# 12_LMS2_Power.net
KiCad netlist of a schematic drawn in Altium Designer
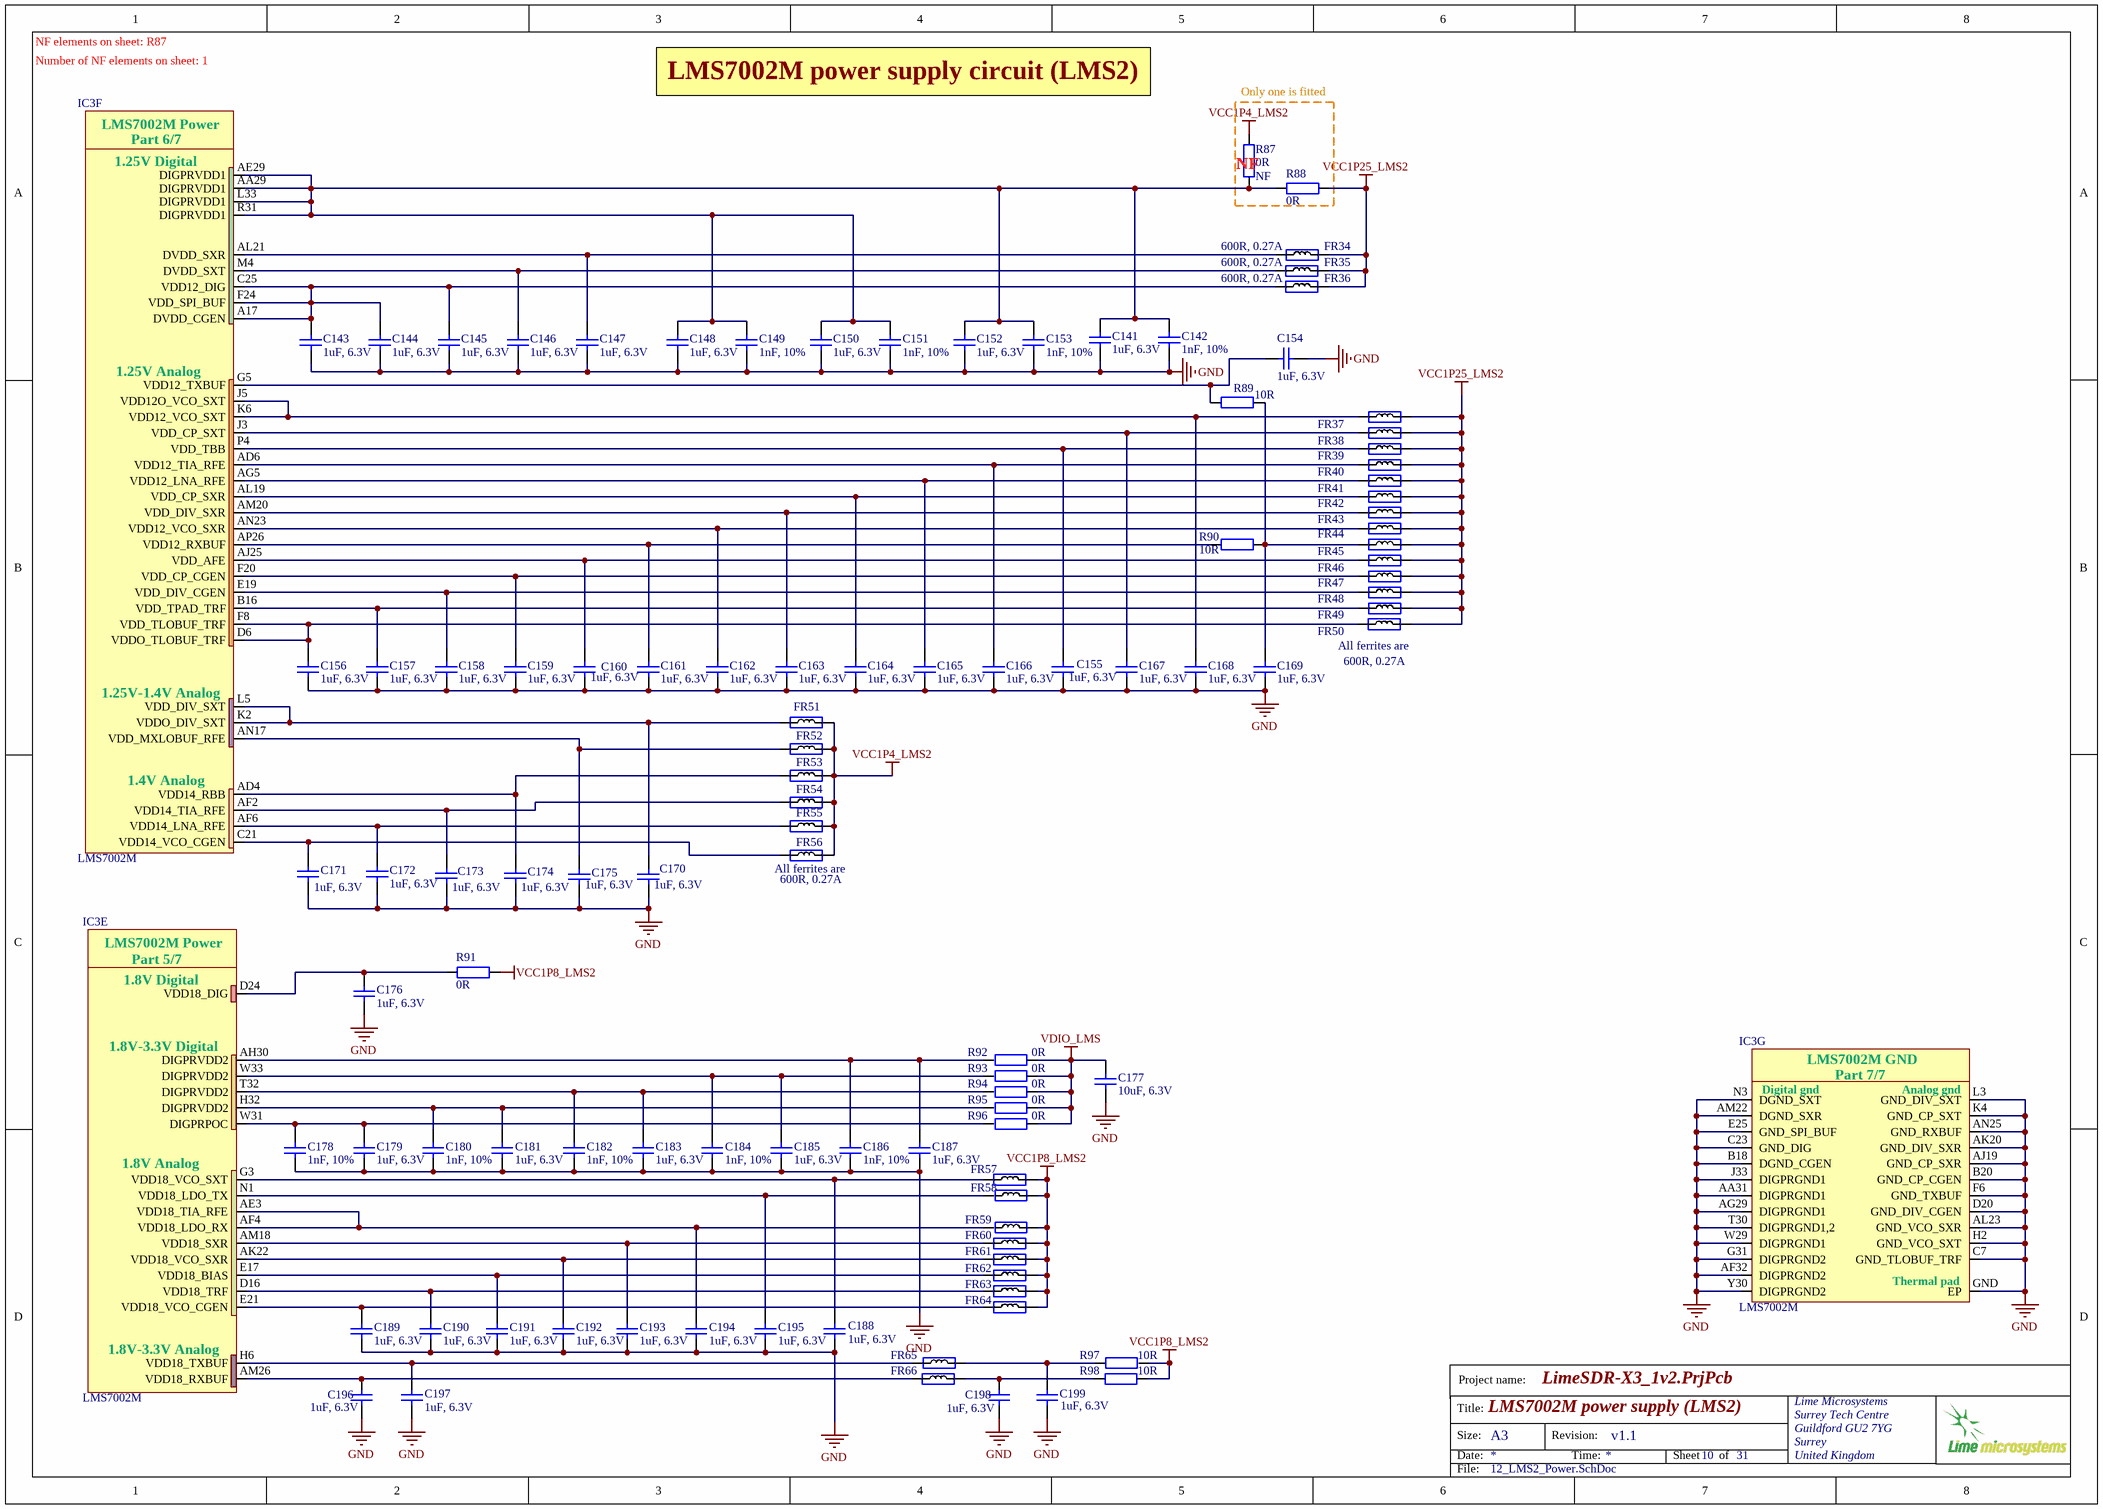
[diagram p0: 12_LMS2_Power.SchDoc]

(export (version "E")
  (design (tool "Eeschema 10.0.6"))
  (components
    (comp (ref "C141")
      (value "1uF, 6.3V")
      (footprint "CAP0201")
      (fields (field (name "TOLERANCE") "±20%") (field (name "MANUFACTURER") "TDK Corporation"))
      (libsource (lib "LimeMicroAltiumLib_schLib") (part "Cap_0402"))
    )
    (comp (ref "C142")
      (value "1nF, 10%")
      (footprint "CAP0201")
      (fields (field (name "TOLERANCE") "±10%") (field (name "MANUFACTURER") "TDK Corporation"))
      (libsource (lib "LimeMicroAltiumLib_schLib") (part "Cap_0402"))
    )
    (comp (ref "C143")
      (value "1uF, 6.3V")
      (footprint "CAP0201")
      (fields (field (name "TOLERANCE") "±20%") (field (name "MANUFACTURER") "TDK Corporation"))
      (libsource (lib "") (part "Cap_0402_2"))
    )
    (comp (ref "C144")
      (value "1uF, 6.3V")
      (footprint "CAP0201")
      (fields (field (name "TOLERANCE") "±20%") (field (name "MANUFACTURER") "TDK Corporation"))
      (libsource (lib "") (part "Cap_0402_2"))
    )
    (comp (ref "C145")
      (value "1uF, 6.3V")
      (footprint "CAP0201")
      (fields (field (name "TOLERANCE") "±20%") (field (name "MANUFACTURER") "TDK Corporation"))
      (libsource (lib "") (part "Cap_0402_2"))
    )
    (comp (ref "C146")
      (value "1uF, 6.3V")
      (footprint "CAP0201")
      (fields (field (name "TOLERANCE") "±20%") (field (name "MANUFACTURER") "TDK Corporation"))
      (libsource (lib "LimeMicroAltiumLib_schLib") (part "Cap_0402"))
    )
    (comp (ref "C147")
      (value "1uF, 6.3V")
      (footprint "CAP0201")
      (fields (field (name "TOLERANCE") "±20%") (field (name "MANUFACTURER") "TDK Corporation"))
      (libsource (lib "") (part "Cap_0402_2"))
    )
    (comp (ref "C148")
      (value "1uF, 6.3V")
      (footprint "CAP0201")
      (fields (field (name "TOLERANCE") "±20%") (field (name "MANUFACTURER") "TDK Corporation"))
      (libsource (lib "LimeMicroAltiumLib_schLib") (part "Cap_0402"))
    )
    (comp (ref "C149")
      (value "1nF, 10%")
      (footprint "CAP0201")
      (fields (field (name "TOLERANCE") "±10%") (field (name "MANUFACTURER") "TDK Corporation"))
      (libsource (lib "LimeMicroAltiumLib_schLib") (part "Cap_0402"))
    )
    (comp (ref "C150")
      (value "1uF, 6.3V")
      (footprint "CAP0201")
      (fields (field (name "TOLERANCE") "±20%") (field (name "MANUFACTURER") "TDK Corporation"))
      (libsource (lib "LimeMicroAltiumLib_schLib") (part "Cap_0402"))
    )
    (comp (ref "C151")
      (value "1nF, 10%")
      (footprint "CAP0201")
      (fields (field (name "TOLERANCE") "±10%") (field (name "MANUFACTURER") "TDK Corporation"))
      (libsource (lib "LimeMicroAltiumLib_schLib") (part "Cap_0402"))
    )
    (comp (ref "C152")
      (value "1uF, 6.3V")
      (footprint "CAP0201")
      (fields (field (name "TOLERANCE") "±20%") (field (name "MANUFACTURER") "TDK Corporation"))
      (libsource (lib "LimeMicroAltiumLib_schLib") (part "Cap_0402"))
    )
    (comp (ref "C153")
      (value "1nF, 10%")
      (footprint "CAP0201")
      (fields (field (name "TOLERANCE") "±10%") (field (name "MANUFACTURER") "TDK Corporation"))
      (libsource (lib "LimeMicroAltiumLib_schLib") (part "Cap_0402"))
    )
    (comp (ref "C154")
      (value "1uF, 6.3V")
      (footprint "CAP0201")
      (fields (field (name "TOLERANCE") "±20%") (field (name "MANUFACTURER") "TDK Corporation"))
      (libsource (lib "") (part "Cap_0402_3"))
    )
    (comp (ref "C155")
      (value "1uF, 6.3V")
      (footprint "CAP0201")
      (fields (field (name "TOLERANCE") "±20%") (field (name "MANUFACTURER") "TDK Corporation"))
      (libsource (lib "") (part "Cap_0402_2"))
    )
    (comp (ref "C156")
      (value "1uF, 6.3V")
      (footprint "CAP0201")
      (fields (field (name "TOLERANCE") "±20%") (field (name "MANUFACTURER") "TDK Corporation"))
      (libsource (lib "") (part "Cap_0402_2"))
    )
    (comp (ref "C157")
      (value "1uF, 6.3V")
      (footprint "CAP0201")
      (fields (field (name "TOLERANCE") "±20%") (field (name "MANUFACTURER") "TDK Corporation"))
      (libsource (lib "") (part "Cap_0402_2"))
    )
    (comp (ref "C158")
      (value "1uF, 6.3V")
      (footprint "CAP0201")
      (fields (field (name "TOLERANCE") "±20%") (field (name "MANUFACTURER") "TDK Corporation"))
      (libsource (lib "") (part "Cap_0402_2"))
    )
    (comp (ref "C159")
      (value "1uF, 6.3V")
      (footprint "CAP0201")
      (fields (field (name "TOLERANCE") "±20%") (field (name "MANUFACTURER") "TDK Corporation"))
      (libsource (lib "LimeMicroAltiumLib_schLib") (part "Cap_0402"))
    )
    (comp (ref "C160")
      (value "1uF, 6.3V")
      (footprint "CAP0201")
      (fields (field (name "TOLERANCE") "±20%") (field (name "MANUFACTURER") "TDK Corporation"))
      (libsource (lib "") (part "Cap_0402_2"))
    )
    (comp (ref "C161")
      (value "1uF, 6.3V")
      (footprint "CAP0201")
      (fields (field (name "TOLERANCE") "±20%") (field (name "MANUFACTURER") "TDK Corporation"))
      (libsource (lib "") (part "Cap_0402_2"))
    )
    (comp (ref "C162")
      (value "1uF, 6.3V")
      (footprint "CAP0201")
      (fields (field (name "TOLERANCE") "±20%") (field (name "MANUFACTURER") "TDK Corporation"))
      (libsource (lib "") (part "Cap_0402_2"))
    )
    (comp (ref "C163")
      (value "1uF, 6.3V")
      (footprint "CAP0201")
      (fields (field (name "TOLERANCE") "±20%") (field (name "MANUFACTURER") "TDK Corporation"))
      (libsource (lib "") (part "Cap_0402_2"))
    )
    (comp (ref "C164")
      (value "1uF, 6.3V")
      (footprint "CAP0201")
      (fields (field (name "TOLERANCE") "±20%") (field (name "MANUFACTURER") "TDK Corporation"))
      (libsource (lib "") (part "Cap_0402_2"))
    )
    (comp (ref "C165")
      (value "1uF, 6.3V")
      (footprint "CAP0201")
      (fields (field (name "TOLERANCE") "±20%") (field (name "MANUFACTURER") "TDK Corporation"))
      (libsource (lib "") (part "Cap_0402_2"))
    )
    (comp (ref "C166")
      (value "1uF, 6.3V")
      (footprint "CAP0201")
      (fields (field (name "TOLERANCE") "±20%") (field (name "MANUFACTURER") "TDK Corporation"))
      (libsource (lib "LimeMicroAltiumLib_schLib") (part "Cap_0402"))
    )
    (comp (ref "C167")
      (value "1uF, 6.3V")
      (footprint "CAP0201")
      (fields (field (name "TOLERANCE") "±20%") (field (name "MANUFACTURER") "TDK Corporation"))
      (libsource (lib "") (part "Cap_0402_2"))
    )
    (comp (ref "C168")
      (value "1uF, 6.3V")
      (footprint "CAP0201")
      (fields (field (name "TOLERANCE") "±20%") (field (name "MANUFACTURER") "TDK Corporation"))
      (libsource (lib "LimeMicroAltiumLib_schLib") (part "Cap_0402"))
    )
    (comp (ref "C169")
      (value "1uF, 6.3V")
      (footprint "CAP0201")
      (fields (field (name "TOLERANCE") "±20%") (field (name "MANUFACTURER") "TDK Corporation"))
      (libsource (lib "LimeMicroAltiumLib_schLib") (part "Cap_0402"))
    )
    (comp (ref "C170")
      (value "1uF, 6.3V")
      (footprint "CAP0201")
      (fields (field (name "TOLERANCE") "±20%") (field (name "MANUFACTURER") "TDK Corporation"))
      (libsource (lib "") (part "Cap_0402_2"))
    )
    (comp (ref "C171")
      (value "1uF, 6.3V")
      (footprint "CAP0201")
      (fields (field (name "TOLERANCE") "±20%") (field (name "MANUFACTURER") "TDK Corporation"))
      (libsource (lib "") (part "Cap_0402_2"))
    )
    (comp (ref "C172")
      (value "1uF, 6.3V")
      (footprint "CAP0201")
      (fields (field (name "TOLERANCE") "±20%") (field (name "MANUFACTURER") "TDK Corporation"))
      (libsource (lib "") (part "Cap_0402_2"))
    )
    (comp (ref "C173")
      (value "1uF, 6.3V")
      (footprint "CAP0201")
      (fields (field (name "TOLERANCE") "±20%") (field (name "MANUFACTURER") "TDK Corporation"))
      (libsource (lib "") (part "Cap_0402_4"))
    )
    (comp (ref "C174")
      (value "1uF, 6.3V")
      (footprint "CAP0201")
      (fields (field (name "TOLERANCE") "±20%") (field (name "MANUFACTURER") "TDK Corporation"))
      (libsource (lib "") (part "Cap_0402_4"))
    )
    (comp (ref "C175")
      (value "1uF, 6.3V")
      (footprint "CAP0201")
      (fields (field (name "TOLERANCE") "±20%") (field (name "MANUFACTURER") "TDK Corporation"))
      (libsource (lib "") (part "Cap_0402_2"))
    )
    (comp (ref "C176")
      (value "1uF, 6.3V")
      (footprint "CAP0201")
      (fields (field (name "TOLERANCE") "±20%") (field (name "MANUFACTURER") "TDK Corporation"))
      (libsource (lib "") (part "Cap_0402_1"))
    )
    (comp (ref "C177")
      (value "10uF, 6.3V")
      (footprint "CAP0603")
      (fields (field (name "TOLERANCE") "±20%") (field (name "MANUFACTURER") "Yageo"))
      (libsource (lib "LimeFPGAboard_schLib") (part "Cap_0603"))
    )
    (comp (ref "C178")
      (value "1nF, 10%")
      (footprint "CAP0201")
      (fields (field (name "TOLERANCE") "±10%") (field (name "MANUFACTURER") "TDK Corporation"))
      (libsource (lib "") (part "Cap_0402_1"))
    )
    (comp (ref "C179")
      (value "1uF, 6.3V")
      (footprint "CAP0201")
      (fields (field (name "TOLERANCE") "±20%") (field (name "MANUFACTURER") "TDK Corporation"))
      (libsource (lib "") (part "Cap_0402_1"))
    )
    (comp (ref "C180")
      (value "1nF, 10%")
      (footprint "CAP0201")
      (fields (field (name "TOLERANCE") "±10%") (field (name "MANUFACTURER") "TDK Corporation"))
      (libsource (lib "") (part "Cap_0402_1"))
    )
    (comp (ref "C181")
      (value "1uF, 6.3V")
      (footprint "CAP0201")
      (fields (field (name "TOLERANCE") "±20%") (field (name "MANUFACTURER") "TDK Corporation"))
      (libsource (lib "") (part "Cap_0402_1"))
    )
    (comp (ref "C182")
      (value "1nF, 10%")
      (footprint "CAP0201")
      (fields (field (name "TOLERANCE") "±10%") (field (name "MANUFACTURER") "TDK Corporation"))
      (libsource (lib "") (part "Cap_0402_1"))
    )
    (comp (ref "C183")
      (value "1uF, 6.3V")
      (footprint "CAP0201")
      (fields (field (name "TOLERANCE") "±20%") (field (name "MANUFACTURER") "TDK Corporation"))
      (libsource (lib "") (part "Cap_0402_1"))
    )
    (comp (ref "C184")
      (value "1nF, 10%")
      (footprint "CAP0201")
      (fields (field (name "TOLERANCE") "±10%") (field (name "MANUFACTURER") "TDK Corporation"))
      (libsource (lib "") (part "Cap_0402_1"))
    )
    (comp (ref "C185")
      (value "1uF, 6.3V")
      (footprint "CAP0201")
      (fields (field (name "TOLERANCE") "±20%") (field (name "MANUFACTURER") "TDK Corporation"))
      (libsource (lib "") (part "Cap_0402_1"))
    )
    (comp (ref "C186")
      (value "1nF, 10%")
      (footprint "CAP0201")
      (fields (field (name "TOLERANCE") "±10%") (field (name "MANUFACTURER") "TDK Corporation"))
      (libsource (lib "") (part "Cap_0402_1"))
    )
    (comp (ref "C187")
      (value "1uF, 6.3V")
      (footprint "CAP0201")
      (fields (field (name "TOLERANCE") "±20%") (field (name "MANUFACTURER") "TDK Corporation"))
      (libsource (lib "") (part "Cap_0402_1"))
    )
    (comp (ref "C188")
      (value "1uF, 6.3V")
      (footprint "CAP0201")
      (fields (field (name "TOLERANCE") "±20%") (field (name "MANUFACTURER") "TDK Corporation"))
      (libsource (lib "") (part "Cap_0402_1"))
    )
    (comp (ref "C189")
      (value "1uF, 6.3V")
      (footprint "CAP0201")
      (fields (field (name "TOLERANCE") "±20%") (field (name "MANUFACTURER") "TDK Corporation"))
      (libsource (lib "") (part "Cap_0402_1"))
    )
    (comp (ref "C190")
      (value "1uF, 6.3V")
      (footprint "CAP0201")
      (fields (field (name "TOLERANCE") "±20%") (field (name "MANUFACTURER") "TDK Corporation"))
      (libsource (lib "") (part "Cap_0402_1"))
    )
    (comp (ref "C191")
      (value "1uF, 6.3V")
      (footprint "CAP0201")
      (fields (field (name "TOLERANCE") "±20%") (field (name "MANUFACTURER") "TDK Corporation"))
      (libsource (lib "") (part "Cap_0402_1"))
    )
    (comp (ref "C192")
      (value "1uF, 6.3V")
      (footprint "CAP0201")
      (fields (field (name "TOLERANCE") "±20%") (field (name "MANUFACTURER") "TDK Corporation"))
      (libsource (lib "") (part "Cap_0402_1"))
    )
    (comp (ref "C193")
      (value "1uF, 6.3V")
      (footprint "CAP0201")
      (fields (field (name "TOLERANCE") "±20%") (field (name "MANUFACTURER") "TDK Corporation"))
      (libsource (lib "") (part "Cap_0402_1"))
    )
    (comp (ref "C194")
      (value "1uF, 6.3V")
      (footprint "CAP0201")
      (fields (field (name "TOLERANCE") "±20%") (field (name "MANUFACTURER") "TDK Corporation"))
      (libsource (lib "") (part "Cap_0402_1"))
    )
    (comp (ref "C195")
      (value "1uF, 6.3V")
      (footprint "CAP0201")
      (fields (field (name "TOLERANCE") "±20%") (field (name "MANUFACTURER") "TDK Corporation"))
      (libsource (lib "") (part "Cap_0402_1"))
    )
    (comp (ref "C196")
      (value "1uF, 6.3V")
      (footprint "CAP0201")
      (fields (field (name "TOLERANCE") "±20%") (field (name "MANUFACTURER") "TDK Corporation"))
      (libsource (lib "") (part "Cap_0402_1"))
    )
    (comp (ref "C197")
      (value "1uF, 6.3V")
      (footprint "CAP0201")
      (fields (field (name "TOLERANCE") "±20%") (field (name "MANUFACTURER") "TDK Corporation"))
      (libsource (lib "") (part "Cap_0402_1"))
    )
    (comp (ref "C198")
      (value "1uF, 6.3V")
      (footprint "CAP0201")
      (fields (field (name "TOLERANCE") "±20%") (field (name "MANUFACTURER") "TDK Corporation"))
      (libsource (lib "") (part "Cap_0402_1"))
    )
    (comp (ref "C199")
      (value "1uF, 6.3V")
      (footprint "CAP0201")
      (fields (field (name "TOLERANCE") "±20%") (field (name "MANUFACTURER") "TDK Corporation"))
      (libsource (lib "") (part "Cap_0402_1"))
    )
    (comp (ref "FR34")
      (value "600R, 0.27A")
      (footprint "RES0201")
      (fields (field (name "MANUFACTURER") "Taiyo Yuden"))
      (libsource (lib "LimeMicroAltiumLib_schLib") (part "Ferrite"))
    )
    (comp (ref "FR35")
      (value "600R, 0.27A")
      (footprint "RES0201")
      (fields (field (name "MANUFACTURER") "Taiyo Yuden"))
      (libsource (lib "") (part "Ferrite_2"))
    )
    (comp (ref "FR36")
      (value "600R, 0.27A")
      (footprint "RES0201")
      (fields (field (name "MANUFACTURER") "Taiyo Yuden"))
      (libsource (lib "") (part "Ferrite_2"))
    )
    (comp (ref "FR37")
      (value "600R, 0.27A")
      (footprint "RES0201")
      (fields (field (name "MANUFACTURER") "Taiyo Yuden"))
      (libsource (lib "LimeMicroAltiumLib_schLib") (part "Ferrite"))
    )
    (comp (ref "FR38")
      (value "600R, 0.27A")
      (footprint "RES0201")
      (fields (field (name "MANUFACTURER") "Taiyo Yuden"))
      (libsource (lib "LimeMicroAltiumLib_schLib") (part "Ferrite"))
    )
    (comp (ref "FR39")
      (value "600R, 0.27A")
      (footprint "RES0201")
      (fields (field (name "MANUFACTURER") "Taiyo Yuden"))
      (libsource (lib "LimeMicroAltiumLib_schLib") (part "Ferrite"))
    )
    (comp (ref "FR40")
      (value "600R, 0.27A")
      (footprint "RES0201")
      (fields (field (name "MANUFACTURER") "Taiyo Yuden"))
      (libsource (lib "LimeMicroAltiumLib_schLib") (part "Ferrite"))
    )
    (comp (ref "FR41")
      (value "600R, 0.27A")
      (footprint "RES0201")
      (fields (field (name "MANUFACTURER") "Taiyo Yuden"))
      (libsource (lib "LimeMicroAltiumLib_schLib") (part "Ferrite"))
    )
    (comp (ref "FR42")
      (value "600R, 0.27A")
      (footprint "RES0201")
      (fields (field (name "MANUFACTURER") "Taiyo Yuden"))
      (libsource (lib "LimeMicroAltiumLib_schLib") (part "Ferrite"))
    )
    (comp (ref "FR43")
      (value "600R, 0.27A")
      (footprint "RES0201")
      (fields (field (name "MANUFACTURER") "Taiyo Yuden"))
      (libsource (lib "LimeMicroAltiumLib_schLib") (part "Ferrite"))
    )
    (comp (ref "FR44")
      (value "600R, 0.27A")
      (footprint "RES0201")
      (fields (field (name "MANUFACTURER") "Taiyo Yuden"))
      (libsource (lib "LimeMicroAltiumLib_schLib") (part "Ferrite"))
    )
    (comp (ref "FR45")
      (value "600R, 0.27A")
      (footprint "RES0201")
      (fields (field (name "MANUFACTURER") "Taiyo Yuden"))
      (libsource (lib "LimeMicroAltiumLib_schLib") (part "Ferrite"))
    )
    (comp (ref "FR46")
      (value "600R, 0.27A")
      (footprint "RES0201")
      (fields (field (name "MANUFACTURER") "Taiyo Yuden"))
      (libsource (lib "LimeMicroAltiumLib_schLib") (part "Ferrite"))
    )
    (comp (ref "FR47")
      (value "600R, 0.27A")
      (footprint "RES0201")
      (fields (field (name "MANUFACTURER") "Taiyo Yuden"))
      (libsource (lib "LimeMicroAltiumLib_schLib") (part "Ferrite"))
    )
    (comp (ref "FR48")
      (value "600R, 0.27A")
      (footprint "RES0201")
      (fields (field (name "MANUFACTURER") "Taiyo Yuden"))
      (libsource (lib "LimeMicroAltiumLib_schLib") (part "Ferrite"))
    )
    (comp (ref "FR49")
      (value "600R, 0.27A")
      (footprint "RES0201")
      (fields (field (name "MANUFACTURER") "Taiyo Yuden"))
      (libsource (lib "LimeMicroAltiumLib_schLib") (part "Ferrite"))
    )
    (comp (ref "FR50")
      (value "600R, 0.27A")
      (footprint "RES0201")
      (fields (field (name "MANUFACTURER") "Taiyo Yuden"))
      (libsource (lib "") (part "Ferrite_2"))
    )
    (comp (ref "FR51")
      (value "600R, 0.27A")
      (footprint "RES0201")
      (fields (field (name "MANUFACTURER") "Taiyo Yuden"))
      (libsource (lib "") (part "Ferrite_2"))
    )
    (comp (ref "FR52")
      (value "600R, 0.27A")
      (footprint "RES0201")
      (fields (field (name "MANUFACTURER") "Taiyo Yuden"))
      (libsource (lib "") (part "Ferrite_2"))
    )
    (comp (ref "FR53")
      (value "600R, 0.27A")
      (footprint "RES0201")
      (fields (field (name "MANUFACTURER") "Taiyo Yuden"))
      (libsource (lib "") (part "Ferrite_2"))
    )
    (comp (ref "FR54")
      (value "600R, 0.27A")
      (footprint "RES0201")
      (fields (field (name "MANUFACTURER") "Taiyo Yuden"))
      (libsource (lib "") (part "Ferrite_2"))
    )
    (comp (ref "FR55")
      (value "600R, 0.27A")
      (footprint "RES0201")
      (fields (field (name "MANUFACTURER") "Taiyo Yuden"))
      (libsource (lib "") (part "Ferrite_2"))
    )
    (comp (ref "FR56")
      (value "600R, 0.27A")
      (footprint "RES0201")
      (fields (field (name "MANUFACTURER") "Taiyo Yuden"))
      (libsource (lib "") (part "Ferrite_2"))
    )
    (comp (ref "FR57")
      (value "600R, 0.27A")
      (footprint "RES0201")
      (fields (field (name "MANUFACTURER") "Taiyo Yuden"))
      (libsource (lib "") (part "Ferrite_2"))
    )
    (comp (ref "FR58")
      (value "600R, 0.27A")
      (footprint "RES0201")
      (fields (field (name "MANUFACTURER") "Taiyo Yuden"))
      (libsource (lib "") (part "Ferrite_1"))
    )
    (comp (ref "FR59")
      (value "600R, 0.27A")
      (footprint "RES0201")
      (fields (field (name "MANUFACTURER") "Taiyo Yuden"))
      (libsource (lib "") (part "Ferrite_1"))
    )
    (comp (ref "FR60")
      (value "600R, 0.27A")
      (footprint "RES0201")
      (fields (field (name "MANUFACTURER") "Taiyo Yuden"))
      (libsource (lib "") (part "Ferrite_2"))
    )
    (comp (ref "FR61")
      (value "600R, 0.27A")
      (footprint "RES0201")
      (fields (field (name "MANUFACTURER") "Taiyo Yuden"))
      (libsource (lib "") (part "Ferrite_2"))
    )
    (comp (ref "FR62")
      (value "600R, 0.27A")
      (footprint "RES0201")
      (fields (field (name "MANUFACTURER") "Taiyo Yuden"))
      (libsource (lib "") (part "Ferrite_2"))
    )
    (comp (ref "FR63")
      (value "600R, 0.27A")
      (footprint "RES0201")
      (fields (field (name "MANUFACTURER") "Taiyo Yuden"))
      (libsource (lib "") (part "Ferrite_2"))
    )
    (comp (ref "FR64")
      (value "600R, 0.27A")
      (footprint "RES0201")
      (fields (field (name "MANUFACTURER") "Taiyo Yuden"))
      (libsource (lib "") (part "Ferrite_2"))
    )
    (comp (ref "FR65")
      (value "600R, 0.27A")
      (footprint "RES0201")
      (fields (field (name "MANUFACTURER") "Taiyo Yuden"))
      (libsource (lib "") (part "Ferrite_1"))
    )
    (comp (ref "FR66")
      (value "600R, 0.27A")
      (footprint "RES0201")
      (fields (field (name "MANUFACTURER") "Taiyo Yuden"))
      (libsource (lib "") (part "Ferrite_2"))
    )
    (comp (ref "IC3")
      (value "LMS7002M")
      (footprint "LMS7002M_v5")
      (description "Schematic symbol revision 4. Default footprint - 0.31mm pad")
      (fields (field (name "MANUFACTURER") "Lime Microsystems"))
      (libsource (lib "LimeMicroAltiumLib_schLib_r04") (part "LMS7002Mr4"))
    )
    (comp (ref "R87")
      (value "0R")
      (footprint "RES0402")
      (fields
        (field (name "ASSEMBLY INFO") "NF")
        (field (name "MANUFACTURER") "Yageo")
        (field (name "TOLERANCE") "Jumper")
      )
      (libsource (lib "LimeMicroAltiumLib_schLib") (part "Res_0402"))
    )
    (comp (ref "R88")
      (value "0R")
      (footprint "RES0402")
      (fields (field (name "MANUFACTURER") "Yageo") (field (name "TOLERANCE") "Jumper"))
      (libsource (lib "") (part "Res_0402_1"))
    )
    (comp (ref "R89")
      (value "10R")
      (footprint "RES0201")
      (fields
        (field (name "MANUFACTURER") "Panasonic Electronic Components")
        (field (name "TOLERANCE") "±1%")
      )
      (libsource (lib "LimeMicroAltiumLib_schLib") (part "Res_0402"))
    )
    (comp (ref "R90")
      (value "10R")
      (footprint "RES0201")
      (fields
        (field (name "MANUFACTURER") "Panasonic Electronic Components")
        (field (name "TOLERANCE") "±1%")
      )
      (libsource (lib "LimeMicroAltiumLib_schLib") (part "Res_0402"))
    )
    (comp (ref "R91")
      (value "0R")
      (footprint "RES0201")
      (fields (field (name "MANUFACTURER") "Rohm Semiconductor") (field (name "TOLERANCE") "Jumper"))
      (libsource (lib "LimeMicroAltiumLib_schLib") (part "Res_0402"))
    )
    (comp (ref "R92")
      (value "0R")
      (footprint "RES0402")
      (fields (field (name "MANUFACTURER") "Yageo") (field (name "TOLERANCE") "Jumper"))
      (libsource (lib "LimeMicroAltiumLib_schLib") (part "Res_0402"))
    )
    (comp (ref "R93")
      (value "0R")
      (footprint "RES0402")
      (fields (field (name "MANUFACTURER") "Yageo") (field (name "TOLERANCE") "Jumper"))
      (libsource (lib "LimeMicroAltiumLib_schLib") (part "Res_0402"))
    )
    (comp (ref "R94")
      (value "0R")
      (footprint "RES0402")
      (fields (field (name "MANUFACTURER") "Yageo") (field (name "TOLERANCE") "Jumper"))
      (libsource (lib "LimeMicroAltiumLib_schLib") (part "Res_0402"))
    )
    (comp (ref "R95")
      (value "0R")
      (footprint "RES0402")
      (fields (field (name "MANUFACTURER") "Yageo") (field (name "TOLERANCE") "Jumper"))
      (libsource (lib "LimeMicroAltiumLib_schLib") (part "Res_0402"))
    )
    (comp (ref "R96")
      (value "0R")
      (footprint "RES0402")
      (fields (field (name "MANUFACTURER") "Yageo") (field (name "TOLERANCE") "Jumper"))
      (libsource (lib "LimeMicroAltiumLib_schLib") (part "Res_0402"))
    )
    (comp (ref "R97")
      (value "10R")
      (footprint "RES0201")
      (fields
        (field (name "MANUFACTURER") "Panasonic Electronic Components")
        (field (name "TOLERANCE") "±1%")
      )
      (libsource (lib "LimeMicroAltiumLib_schLib") (part "Res_0402"))
    )
    (comp (ref "R98")
      (value "10R")
      (footprint "RES0201")
      (fields
        (field (name "MANUFACTURER") "Panasonic Electronic Components")
        (field (name "TOLERANCE") "±1%")
      )
      (libsource (lib "LimeMicroAltiumLib_schLib") (part "Res_0402"))
    )
  )
  (nets
    (net (code "1") (name "GND") (class "Default")
      (node (ref "C141") (pin "2") (pinfunction "2_2") (pintype "passive"))
      (node (ref "C142") (pin "2") (pinfunction "2_2") (pintype "passive"))
      (node (ref "C143") (pin "2") (pinfunction "2_2") (pintype "passive"))
      (node (ref "C144") (pin "2") (pinfunction "2_2") (pintype "passive"))
      (node (ref "C145") (pin "2") (pinfunction "2_2") (pintype "passive"))
      (node (ref "C146") (pin "1") (pinfunction "1_1") (pintype "passive"))
      (node (ref "C147") (pin "2") (pinfunction "2_2") (pintype "passive"))
      (node (ref "C148") (pin "2") (pinfunction "2_2") (pintype "passive"))
      (node (ref "C149") (pin "2") (pinfunction "2_2") (pintype "passive"))
      (node (ref "C150") (pin "2") (pinfunction "2_2") (pintype "passive"))
      (node (ref "C151") (pin "2") (pinfunction "2_2") (pintype "passive"))
      (node (ref "C152") (pin "2") (pinfunction "2_2") (pintype "passive"))
      (node (ref "C153") (pin "2") (pinfunction "2_2") (pintype "passive"))
      (node (ref "C154") (pin "2") (pinfunction "2_2") (pintype "passive"))
      (node (ref "C155") (pin "2") (pinfunction "2_2") (pintype "passive"))
      (node (ref "C156") (pin "2") (pinfunction "2_2") (pintype "passive"))
      (node (ref "C157") (pin "2") (pinfunction "2_2") (pintype "passive"))
      (node (ref "C158") (pin "2") (pinfunction "2_2") (pintype "passive"))
      (node (ref "C159") (pin "1") (pinfunction "1_1") (pintype "passive"))
      (node (ref "C160") (pin "2") (pinfunction "2_2") (pintype "passive"))
      (node (ref "C161") (pin "2") (pinfunction "2_2") (pintype "passive"))
      (node (ref "C162") (pin "2") (pinfunction "2_2") (pintype "passive"))
      (node (ref "C163") (pin "2") (pinfunction "2_2") (pintype "passive"))
      (node (ref "C164") (pin "2") (pinfunction "2_2") (pintype "passive"))
      (node (ref "C165") (pin "2") (pinfunction "2_2") (pintype "passive"))
      (node (ref "C166") (pin "1") (pinfunction "1_1") (pintype "passive"))
      (node (ref "C167") (pin "2") (pinfunction "2_2") (pintype "passive"))
      (node (ref "C168") (pin "1") (pinfunction "1_1") (pintype "passive"))
      (node (ref "C169") (pin "1") (pinfunction "1_1") (pintype "passive"))
      (node (ref "C170") (pin "2") (pinfunction "2_2") (pintype "passive"))
      (node (ref "C171") (pin "2") (pinfunction "2_2") (pintype "passive"))
      (node (ref "C172") (pin "2") (pinfunction "2_2") (pintype "passive"))
      (node (ref "C173") (pin "2") (pinfunction "2_2") (pintype "passive"))
      (node (ref "C174") (pin "2") (pinfunction "2_2") (pintype "passive"))
      (node (ref "C175") (pin "2") (pinfunction "2_2") (pintype "passive"))
      (node (ref "C176") (pin "2") (pinfunction "2_2") (pintype "passive"))
      (node (ref "C177") (pin "1") (pinfunction "1_1") (pintype "passive"))
      (node (ref "C178") (pin "2") (pinfunction "2_2") (pintype "passive"))
      (node (ref "C179") (pin "2") (pinfunction "2_2") (pintype "passive"))
      (node (ref "C180") (pin "2") (pinfunction "2_2") (pintype "passive"))
      (node (ref "C181") (pin "2") (pinfunction "2_2") (pintype "passive"))
      (node (ref "C182") (pin "2") (pinfunction "2_2") (pintype "passive"))
      (node (ref "C183") (pin "2") (pinfunction "2_2") (pintype "passive"))
      (node (ref "C184") (pin "2") (pinfunction "2_2") (pintype "passive"))
      (node (ref "C185") (pin "2") (pinfunction "2_2") (pintype "passive"))
      (node (ref "C186") (pin "2") (pinfunction "2_2") (pintype "passive"))
      (node (ref "C187") (pin "2") (pinfunction "2_2") (pintype "passive"))
      (node (ref "C188") (pin "2") (pinfunction "2_2") (pintype "passive"))
      (node (ref "C189") (pin "2") (pinfunction "2_2") (pintype "passive"))
      (node (ref "C190") (pin "2") (pinfunction "2_2") (pintype "passive"))
      (node (ref "C191") (pin "2") (pinfunction "2_2") (pintype "passive"))
      (node (ref "C192") (pin "2") (pinfunction "2_2") (pintype "passive"))
      (node (ref "C193") (pin "2") (pinfunction "2_2") (pintype "passive"))
      (node (ref "C194") (pin "2") (pinfunction "2_2") (pintype "passive"))
      (node (ref "C195") (pin "2") (pinfunction "2_2") (pintype "passive"))
      (node (ref "C196") (pin "2") (pinfunction "2_2") (pintype "passive"))
      (node (ref "C197") (pin "2") (pinfunction "2_2") (pintype "passive"))
      (node (ref "C198") (pin "2") (pinfunction "2_2") (pintype "passive"))
      (node (ref "C199") (pin "2") (pinfunction "2_2") (pintype "passive"))
      (node (ref "IC3") (pin "AA31") (pinfunction "DIGPRGND1_AA31") (pintype "passive"))
      (node (ref "IC3") (pin "AF32") (pinfunction "DIGPRGND2_AF32") (pintype "passive"))
      (node (ref "IC3") (pin "AG29") (pinfunction "DIGPRGND1_AG29") (pintype "passive"))
      (node (ref "IC3") (pin "AJ19") (pinfunction "GND_CP_SXR_AJ19") (pintype "passive"))
      (node (ref "IC3") (pin "AK20") (pinfunction "GND_DIV_SXR_AK20") (pintype "passive"))
      (node (ref "IC3") (pin "AL23") (pinfunction "GND_VCO_SXR_AL23") (pintype "passive"))
      (node (ref "IC3") (pin "AM22") (pinfunction "DGND_SXR_AM22") (pintype "passive"))
      (node (ref "IC3") (pin "AN25") (pinfunction "GND_RXBUF_AN25") (pintype "passive"))
      (node (ref "IC3") (pin "B18") (pinfunction "DGND_CGEN_B18") (pintype "passive"))
      (node (ref "IC3") (pin "B20") (pinfunction "GND_CP_CGEN_B20") (pintype "passive"))
      (node (ref "IC3") (pin "C23") (pinfunction "GND_DIG_C23") (pintype "passive"))
      (node (ref "IC3") (pin "C7") (pinfunction "GND_TLOBUF_TRF_C7") (pintype "passive"))
      (node (ref "IC3") (pin "D20") (pinfunction "GND_DIV_CGEN_D20") (pintype "passive"))
      (node (ref "IC3") (pin "E25") (pinfunction "GND_SPI_BUF_E25") (pintype "passive"))
      (node (ref "IC3") (pin "F6") (pinfunction "GND_TXBUF_F6") (pintype "passive"))
      (node (ref "IC3") (pin "G31") (pinfunction "DIGPRGND2_G31") (pintype "passive"))
      (node (ref "IC3") (pin "GND") (pinfunction "EP_GND") (pintype "passive"))
      (node (ref "IC3") (pin "H2") (pinfunction "GND_VCO_SXT_H2") (pintype "passive"))
      (node (ref "IC3") (pin "J33") (pinfunction "DIGPRGND1_J33") (pintype "passive"))
      (node (ref "IC3") (pin "K4") (pinfunction "GND_CP_SXT_K4") (pintype "passive"))
      (node (ref "IC3") (pin "L3") (pinfunction "GND_DIV_SXT_L3") (pintype "passive"))
      (node (ref "IC3") (pin "N3") (pinfunction "DGND_SXT_N3") (pintype "passive"))
      (node (ref "IC3") (pin "T30") (pinfunction "DIGPRGND1,2_T30") (pintype "passive"))
      (node (ref "IC3") (pin "W29") (pinfunction "DIGPRGND1_W29") (pintype "passive"))
      (node (ref "IC3") (pin "Y30") (pinfunction "DIGPRGND2_Y30") (pintype "passive"))
    )
    (net (code "2") (name "Net-(C141-Pad1)") (class "Default")
      (node (ref "C141") (pin "1") (pinfunction "1_1") (pintype "passive"))
      (node (ref "C142") (pin "1") (pinfunction "1_1") (pintype "passive"))
      (node (ref "C148") (pin "1") (pinfunction "1_1") (pintype "passive"))
      (node (ref "C149") (pin "1") (pinfunction "1_1") (pintype "passive"))
      (node (ref "C150") (pin "1") (pinfunction "1_1") (pintype "passive"))
      (node (ref "C151") (pin "1") (pinfunction "1_1") (pintype "passive"))
      (node (ref "C152") (pin "1") (pinfunction "1_1") (pintype "passive"))
      (node (ref "C153") (pin "1") (pinfunction "1_1") (pintype "passive"))
      (node (ref "IC3") (pin "AA29") (pinfunction "DIGPRVDD1_AA29") (pintype "power_in"))
      (node (ref "IC3") (pin "AE29") (pinfunction "DIGPRVDD1_AE29") (pintype "power_in"))
      (node (ref "IC3") (pin "L33") (pinfunction "DIGPRVDD1_L33") (pintype "power_in"))
      (node (ref "IC3") (pin "R31") (pinfunction "DIGPRVDD1_R31") (pintype "power_in"))
      (node (ref "R87") (pin "2") (pinfunction "2_2") (pintype "passive"))
      (node (ref "R88") (pin "2") (pinfunction "2_2") (pintype "passive"))
    )
    (net (code "3") (name "Net-(C169-Pad2)") (class "Default")
      (node (ref "C169") (pin "2") (pinfunction "2_2") (pintype "passive"))
      (node (ref "FR45") (pin "1") (pinfunction "1_1") (pintype "passive"))
      (node (ref "R89") (pin "2") (pinfunction "2_2") (pintype "passive"))
      (node (ref "R90") (pin "2") (pinfunction "2_2") (pintype "passive"))
    )
    (net (code "4") (name "Net-(C180-Pad1)") (class "Default")
      (node (ref "C180") (pin "1") (pinfunction "1_1") (pintype "passive"))
      (node (ref "C181") (pin "1") (pinfunction "1_1") (pintype "passive"))
      (node (ref "IC3") (pin "H32") (pinfunction "DIGPRVDD2_H32") (pintype "power_in"))
      (node (ref "R95") (pin "2") (pinfunction "2_2") (pintype "passive"))
    )
    (net (code "5") (name "Net-(C182-Pad1)") (class "Default")
      (node (ref "C182") (pin "1") (pinfunction "1_1") (pintype "passive"))
      (node (ref "C183") (pin "1") (pinfunction "1_1") (pintype "passive"))
      (node (ref "IC3") (pin "T32") (pinfunction "DIGPRVDD2_T32") (pintype "power_in"))
      (node (ref "R94") (pin "2") (pinfunction "2_2") (pintype "passive"))
    )
    (net (code "6") (name "Net-(C184-Pad1)") (class "Default")
      (node (ref "C184") (pin "1") (pinfunction "1_1") (pintype "passive"))
      (node (ref "C185") (pin "1") (pinfunction "1_1") (pintype "passive"))
      (node (ref "IC3") (pin "W33") (pinfunction "DIGPRVDD2_W33") (pintype "power_in"))
      (node (ref "R93") (pin "2") (pinfunction "2_2") (pintype "passive"))
    )
    (net (code "7") (name "Net-(C186-Pad1)") (class "Default")
      (node (ref "C186") (pin "1") (pinfunction "1_1") (pintype "passive"))
      (node (ref "C187") (pin "1") (pinfunction "1_1") (pintype "passive"))
      (node (ref "IC3") (pin "AH30") (pinfunction "DIGPRVDD2_AH30") (pintype "power_in"))
      (node (ref "R92") (pin "2") (pinfunction "2_2") (pintype "passive"))
    )
    (net (code "8") (name "Net-(C198-Pad1)") (class "Default")
      (node (ref "C198") (pin "1") (pinfunction "1_1") (pintype "passive"))
      (node (ref "FR66") (pin "2") (pinfunction "2_2") (pintype "passive"))
      (node (ref "R98") (pin "2") (pinfunction "2_2") (pintype "passive"))
    )
    (net (code "9") (name "Net-(C199-Pad1)") (class "Default")
      (node (ref "C199") (pin "1") (pinfunction "1_1") (pintype "passive"))
      (node (ref "FR65") (pin "1") (pinfunction "1_1") (pintype "passive"))
      (node (ref "R97") (pin "1") (pinfunction "1_1") (pintype "passive"))
    )
    (net (code "10") (name "Net-(IC3E-DIGPRPOC)") (class "Default")
      (node (ref "C178") (pin "1") (pinfunction "1_1") (pintype "passive"))
      (node (ref "C179") (pin "1") (pinfunction "1_1") (pintype "passive"))
      (node (ref "IC3") (pin "W31") (pinfunction "DIGPRPOC_W31") (pintype "power_in"))
      (node (ref "R96") (pin "2") (pinfunction "2_2") (pintype "passive"))
    )
    (net (code "11") (name "Net-(IC3E-VDD18_BIAS)") (class "Default")
      (node (ref "C191") (pin "1") (pinfunction "1_1") (pintype "passive"))
      (node (ref "FR62") (pin "1") (pinfunction "1_1") (pintype "passive"))
      (node (ref "IC3") (pin "E17") (pinfunction "VDD18_BIAS_E17") (pintype "power_in"))
    )
    (net (code "12") (name "Net-(IC3E-VDD18_DIG)") (class "Default")
      (node (ref "C176") (pin "1") (pinfunction "1_1") (pintype "passive"))
      (node (ref "IC3") (pin "D24") (pinfunction "VDD18_DIG_D24") (pintype "power_in"))
      (node (ref "R91") (pin "1") (pinfunction "1_1") (pintype "passive"))
    )
    (net (code "13") (name "Net-(IC3E-VDD18_LDO_RX)") (class "Default")
      (node (ref "C194") (pin "1") (pinfunction "1_1") (pintype "passive"))
      (node (ref "FR59") (pin "2") (pinfunction "2_2") (pintype "passive"))
      (node (ref "IC3") (pin "AE3") (pinfunction "VDD18_TIA_RFE_AE3") (pintype "power_in"))
      (node (ref "IC3") (pin "AF4") (pinfunction "VDD18_LDO_RX_AF4") (pintype "power_in"))
    )
    (net (code "14") (name "Net-(IC3E-VDD18_LDO_TX)") (class "Default")
      (node (ref "C195") (pin "1") (pinfunction "1_1") (pintype "passive"))
      (node (ref "FR58") (pin "2") (pinfunction "2_2") (pintype "passive"))
      (node (ref "IC3") (pin "N1") (pinfunction "VDD18_LDO_TX_N1") (pintype "power_in"))
    )
    (net (code "15") (name "Net-(IC3E-VDD18_RXBUF)") (class "Default")
      (node (ref "C196") (pin "1") (pinfunction "1_1") (pintype "passive"))
      (node (ref "FR66") (pin "1") (pinfunction "1_1") (pintype "passive"))
      (node (ref "IC3") (pin "AM26") (pinfunction "VDD18_RXBUF_AM26") (pintype "power_in"))
    )
    (net (code "16") (name "Net-(IC3E-VDD18_SXR)") (class "Default")
      (node (ref "C193") (pin "1") (pinfunction "1_1") (pintype "passive"))
      (node (ref "FR60") (pin "1") (pinfunction "1_1") (pintype "passive"))
      (node (ref "IC3") (pin "AM18") (pinfunction "VDD18_SXR_AM18") (pintype "power_in"))
    )
    (net (code "17") (name "Net-(IC3E-VDD18_TRF)") (class "Default")
      (node (ref "C190") (pin "1") (pinfunction "1_1") (pintype "passive"))
      (node (ref "FR63") (pin "1") (pinfunction "1_1") (pintype "passive"))
      (node (ref "IC3") (pin "D16") (pinfunction "VDD18_TRF_D16") (pintype "power_in"))
    )
    (net (code "18") (name "Net-(IC3E-VDD18_TXBUF)") (class "Default")
      (node (ref "C197") (pin "1") (pinfunction "1_1") (pintype "passive"))
      (node (ref "FR65") (pin "2") (pinfunction "2_2") (pintype "passive"))
      (node (ref "IC3") (pin "H6") (pinfunction "VDD18_TXBUF_H6") (pintype "power_in"))
    )
    (net (code "19") (name "Net-(IC3E-VDD18_VCO_CGEN)") (class "Default")
      (node (ref "C189") (pin "1") (pinfunction "1_1") (pintype "passive"))
      (node (ref "FR64") (pin "1") (pinfunction "1_1") (pintype "passive"))
      (node (ref "IC3") (pin "E21") (pinfunction "VDD18_VCO_CGEN_E21") (pintype "power_in"))
    )
    (net (code "20") (name "Net-(IC3E-VDD18_VCO_SXR)") (class "Default")
      (node (ref "C192") (pin "1") (pinfunction "1_1") (pintype "passive"))
      (node (ref "FR61") (pin "1") (pinfunction "1_1") (pintype "passive"))
      (node (ref "IC3") (pin "AK22") (pinfunction "VDD18_VCO_SXR_AK22") (pintype "power_in"))
    )
    (net (code "21") (name "Net-(IC3E-VDD18_VCO_SXT)") (class "Default")
      (node (ref "C188") (pin "1") (pinfunction "1_1") (pintype "passive"))
      (node (ref "FR57") (pin "1") (pinfunction "1_1") (pintype "passive"))
      (node (ref "IC3") (pin "G3") (pinfunction "VDD18_VCO_SXT_G3") (pintype "power_in"))
    )
    (net (code "22") (name "Net-(IC3F-DVDD_CGEN)") (class "Default")
      (node (ref "C143") (pin "1") (pinfunction "1_1") (pintype "passive"))
      (node (ref "C144") (pin "1") (pinfunction "1_1") (pintype "passive"))
      (node (ref "C145") (pin "1") (pinfunction "1_1") (pintype "passive"))
      (node (ref "FR36") (pin "1") (pinfunction "1_1") (pintype "passive"))
      (node (ref "IC3") (pin "A17") (pinfunction "DVDD_CGEN_A17") (pintype "power_in"))
      (node (ref "IC3") (pin "C25") (pinfunction "VDD12_DIG_C25") (pintype "power_in"))
      (node (ref "IC3") (pin "F24") (pinfunction "VDD_SPI_BUF_F24") (pintype "power_in"))
    )
    (net (code "23") (name "Net-(IC3F-DVDD_SXR)") (class "Default")
      (node (ref "C147") (pin "1") (pinfunction "1_1") (pintype "passive"))
      (node (ref "FR34") (pin "1") (pinfunction "1_1") (pintype "passive"))
      (node (ref "IC3") (pin "AL21") (pinfunction "DVDD_SXR_AL21") (pintype "power_in"))
    )
    (net (code "24") (name "Net-(IC3F-DVDD_SXT)") (class "Default")
      (node (ref "C146") (pin "2") (pinfunction "2_2") (pintype "passive"))
      (node (ref "FR35") (pin "1") (pinfunction "1_1") (pintype "passive"))
      (node (ref "IC3") (pin "M4") (pinfunction "DVDD_SXT_M4") (pintype "power_in"))
    )
    (net (code "25") (name "Net-(IC3F-VDD12O_VCO_SXT)") (class "Default")
      (node (ref "C168") (pin "2") (pinfunction "2_2") (pintype "passive"))
      (node (ref "FR37") (pin "1") (pinfunction "1_1") (pintype "passive"))
      (node (ref "IC3") (pin "J5") (pinfunction "VDD12O_VCO_SXT_J5") (pintype "power_in"))
      (node (ref "IC3") (pin "K6") (pinfunction "VDD12_VCO_SXT_K6") (pintype "power_in"))
    )
    (net (code "26") (name "Net-(IC3F-VDD12_LNA_RFE)") (class "Default")
      (node (ref "C165") (pin "1") (pinfunction "1_1") (pintype "passive"))
      (node (ref "FR41") (pin "1") (pinfunction "1_1") (pintype "passive"))
      (node (ref "IC3") (pin "AG5") (pinfunction "VDD12_LNA_RFE_AG5") (pintype "power_in"))
    )
    (net (code "27") (name "Net-(IC3F-VDD12_RXBUF)") (class "Default")
      (node (ref "C161") (pin "1") (pinfunction "1_1") (pintype "passive"))
      (node (ref "IC3") (pin "AP26") (pinfunction "VDD12_RXBUF_AP26") (pintype "power_in"))
      (node (ref "R90") (pin "1") (pinfunction "1_1") (pintype "passive"))
    )
    (net (code "28") (name "Net-(IC3F-VDD12_TIA_RFE)") (class "Default")
      (node (ref "C166") (pin "2") (pinfunction "2_2") (pintype "passive"))
      (node (ref "FR40") (pin "1") (pinfunction "1_1") (pintype "passive"))
      (node (ref "IC3") (pin "AD6") (pinfunction "VDD12_TIA_RFE_AD6") (pintype "power_in"))
    )
    (net (code "29") (name "Net-(IC3F-VDD12_TXBUF)") (class "Default")
      (node (ref "C154") (pin "1") (pinfunction "1_1") (pintype "passive"))
      (node (ref "IC3") (pin "G5") (pinfunction "VDD12_TXBUF_G5") (pintype "power_in"))
      (node (ref "R89") (pin "1") (pinfunction "1_1") (pintype "passive"))
    )
    (net (code "30") (name "Net-(IC3F-VDD12_VCO_SXR)") (class "Default")
      (node (ref "C162") (pin "1") (pinfunction "1_1") (pintype "passive"))
      (node (ref "FR44") (pin "1") (pinfunction "1_1") (pintype "passive"))
      (node (ref "IC3") (pin "AN23") (pinfunction "VDD12_VCO_SXR_AN23") (pintype "power_in"))
    )
    (net (code "31") (name "Net-(IC3F-VDD14_LNA_RFE)") (class "Default")
      (node (ref "C172") (pin "1") (pinfunction "1_1") (pintype "passive"))
      (node (ref "FR55") (pin "1") (pinfunction "1_1") (pintype "passive"))
      (node (ref "IC3") (pin "AF6") (pinfunction "VDD14_LNA_RFE_AF6") (pintype "power_in"))
    )
    (net (code "32") (name "Net-(IC3F-VDD14_RBB)") (class "Default")
      (node (ref "C174") (pin "1") (pinfunction "1_1") (pintype "passive"))
      (node (ref "FR53") (pin "1") (pinfunction "1_1") (pintype "passive"))
      (node (ref "IC3") (pin "AD4") (pinfunction "VDD14_RBB_AD4") (pintype "power_in"))
    )
    (net (code "33") (name "Net-(IC3F-VDD14_TIA_RFE)") (class "Default")
      (node (ref "C173") (pin "1") (pinfunction "1_1") (pintype "passive"))
      (node (ref "FR54") (pin "1") (pinfunction "1_1") (pintype "passive"))
      (node (ref "IC3") (pin "AF2") (pinfunction "VDD14_TIA_RFE_AF2") (pintype "power_in"))
    )
    (net (code "34") (name "Net-(IC3F-VDD14_VCO_CGEN)") (class "Default")
      (node (ref "C171") (pin "1") (pinfunction "1_1") (pintype "passive"))
      (node (ref "FR56") (pin "1") (pinfunction "1_1") (pintype "passive"))
      (node (ref "IC3") (pin "C21") (pinfunction "VDD14_VCO_CGEN_C21") (pintype "power_in"))
    )
    (net (code "35") (name "Net-(IC3F-VDDO_DIV_SXT)") (class "Default")
      (node (ref "C170") (pin "1") (pinfunction "1_1") (pintype "passive"))
      (node (ref "FR51") (pin "1") (pinfunction "1_1") (pintype "passive"))
      (node (ref "IC3") (pin "K2") (pinfunction "VDDO_DIV_SXT_K2") (pintype "power_in"))
      (node (ref "IC3") (pin "L5") (pinfunction "VDD_DIV_SXT_L5") (pintype "power_in"))
    )
    (net (code "36") (name "Net-(IC3F-VDDO_TLOBUF_TRF)") (class "Default")
      (node (ref "C156") (pin "1") (pinfunction "1_1") (pintype "passive"))
      (node (ref "FR50") (pin "1") (pinfunction "1_1") (pintype "passive"))
      (node (ref "IC3") (pin "D6") (pinfunction "VDDO_TLOBUF_TRF_D6") (pintype "power_in"))
      (node (ref "IC3") (pin "F8") (pinfunction "VDD_TLOBUF_TRF_F8") (pintype "power_in"))
    )
    (net (code "37") (name "Net-(IC3F-VDD_AFE)") (class "Default")
      (node (ref "C160") (pin "1") (pinfunction "1_1") (pintype "passive"))
      (node (ref "FR46") (pin "1") (pinfunction "1_1") (pintype "passive"))
      (node (ref "IC3") (pin "AJ25") (pinfunction "VDD_AFE_AJ25") (pintype "power_in"))
    )
    (net (code "38") (name "Net-(IC3F-VDD_CP_CGEN)") (class "Default")
      (node (ref "C159") (pin "2") (pinfunction "2_2") (pintype "passive"))
      (node (ref "FR47") (pin "1") (pinfunction "1_1") (pintype "passive"))
      (node (ref "IC3") (pin "F20") (pinfunction "VDD_CP_CGEN_F20") (pintype "power_in"))
    )
    (net (code "39") (name "Net-(IC3F-VDD_CP_SXR)") (class "Default")
      (node (ref "C164") (pin "1") (pinfunction "1_1") (pintype "passive"))
      (node (ref "FR42") (pin "1") (pinfunction "1_1") (pintype "passive"))
      (node (ref "IC3") (pin "AL19") (pinfunction "VDD_CP_SXR_AL19") (pintype "power_in"))
    )
    (net (code "40") (name "Net-(IC3F-VDD_CP_SXT)") (class "Default")
      (node (ref "C167") (pin "1") (pinfunction "1_1") (pintype "passive"))
      (node (ref "FR38") (pin "1") (pinfunction "1_1") (pintype "passive"))
      (node (ref "IC3") (pin "J3") (pinfunction "VDD_CP_SXT_J3") (pintype "power_in"))
    )
    (net (code "41") (name "Net-(IC3F-VDD_DIV_CGEN)") (class "Default")
      (node (ref "C158") (pin "1") (pinfunction "1_1") (pintype "passive"))
      (node (ref "FR48") (pin "1") (pinfunction "1_1") (pintype "passive"))
      (node (ref "IC3") (pin "E19") (pinfunction "VDD_DIV_CGEN_E19") (pintype "power_in"))
    )
    (net (code "42") (name "Net-(IC3F-VDD_DIV_SXR)") (class "Default")
      (node (ref "C163") (pin "1") (pinfunction "1_1") (pintype "passive"))
      (node (ref "FR43") (pin "1") (pinfunction "1_1") (pintype "passive"))
      (node (ref "IC3") (pin "AM20") (pinfunction "VDD_DIV_SXR_AM20") (pintype "power_in"))
    )
    (net (code "43") (name "Net-(IC3F-VDD_MXLOBUF_RFE)") (class "Default")
      (node (ref "C175") (pin "1") (pinfunction "1_1") (pintype "passive"))
      (node (ref "FR52") (pin "1") (pinfunction "1_1") (pintype "passive"))
      (node (ref "IC3") (pin "AN17") (pinfunction "VDD_MXLOBUF_RFE_AN17") (pintype "power_in"))
    )
    (net (code "44") (name "Net-(IC3F-VDD_TBB)") (class "Default")
      (node (ref "C155") (pin "1") (pinfunction "1_1") (pintype "passive"))
      (node (ref "FR39") (pin "1") (pinfunction "1_1") (pintype "passive"))
      (node (ref "IC3") (pin "P4") (pinfunction "VDD_TBB_P4") (pintype "power_in"))
    )
    (net (code "45") (name "Net-(IC3F-VDD_TPAD_TRF)") (class "Default")
      (node (ref "C157") (pin "1") (pinfunction "1_1") (pintype "passive"))
      (node (ref "FR49") (pin "1") (pinfunction "1_1") (pintype "passive"))
      (node (ref "IC3") (pin "B16") (pinfunction "VDD_TPAD_TRF_B16") (pintype "power_in"))
    )
    (net (code "46") (name "VCC1P4_LMS2") (class "Default")
      (node (ref "FR51") (pin "2") (pinfunction "2_2") (pintype "passive"))
      (node (ref "FR52") (pin "2") (pinfunction "2_2") (pintype "passive"))
      (node (ref "FR53") (pin "2") (pinfunction "2_2") (pintype "passive"))
      (node (ref "FR54") (pin "2") (pinfunction "2_2") (pintype "passive"))
      (node (ref "FR55") (pin "2") (pinfunction "2_2") (pintype "passive"))
      (node (ref "FR56") (pin "2") (pinfunction "2_2") (pintype "passive"))
      (node (ref "R87") (pin "1") (pinfunction "1_1") (pintype "passive"))
    )
    (net (code "47") (name "VCC1P8_LMS2") (class "Default")
      (node (ref "FR57") (pin "2") (pinfunction "2_2") (pintype "passive"))
      (node (ref "FR58") (pin "1") (pinfunction "1_1") (pintype "passive"))
      (node (ref "FR59") (pin "1") (pinfunction "1_1") (pintype "passive"))
      (node (ref "FR60") (pin "2") (pinfunction "2_2") (pintype "passive"))
      (node (ref "FR61") (pin "2") (pinfunction "2_2") (pintype "passive"))
      (node (ref "FR62") (pin "2") (pinfunction "2_2") (pintype "passive"))
      (node (ref "FR63") (pin "2") (pinfunction "2_2") (pintype "passive"))
      (node (ref "FR64") (pin "2") (pinfunction "2_2") (pintype "passive"))
      (node (ref "R91") (pin "2") (pinfunction "2_2") (pintype "passive"))
      (node (ref "R97") (pin "2") (pinfunction "2_2") (pintype "passive"))
      (node (ref "R98") (pin "1") (pinfunction "1_1") (pintype "passive"))
    )
    (net (code "48") (name "VCC1P25_LMS2") (class "Default")
      (node (ref "FR34") (pin "2") (pinfunction "2_2") (pintype "passive"))
      (node (ref "FR35") (pin "2") (pinfunction "2_2") (pintype "passive"))
      (node (ref "FR36") (pin "2") (pinfunction "2_2") (pintype "passive"))
      (node (ref "FR37") (pin "2") (pinfunction "2_2") (pintype "passive"))
      (node (ref "FR38") (pin "2") (pinfunction "2_2") (pintype "passive"))
      (node (ref "FR39") (pin "2") (pinfunction "2_2") (pintype "passive"))
      (node (ref "FR40") (pin "2") (pinfunction "2_2") (pintype "passive"))
      (node (ref "FR41") (pin "2") (pinfunction "2_2") (pintype "passive"))
      (node (ref "FR42") (pin "2") (pinfunction "2_2") (pintype "passive"))
      (node (ref "FR43") (pin "2") (pinfunction "2_2") (pintype "passive"))
      (node (ref "FR44") (pin "2") (pinfunction "2_2") (pintype "passive"))
      (node (ref "FR45") (pin "2") (pinfunction "2_2") (pintype "passive"))
      (node (ref "FR46") (pin "2") (pinfunction "2_2") (pintype "passive"))
      (node (ref "FR47") (pin "2") (pinfunction "2_2") (pintype "passive"))
      (node (ref "FR48") (pin "2") (pinfunction "2_2") (pintype "passive"))
      (node (ref "FR49") (pin "2") (pinfunction "2_2") (pintype "passive"))
      (node (ref "FR50") (pin "2") (pinfunction "2_2") (pintype "passive"))
      (node (ref "R88") (pin "1") (pinfunction "1_1") (pintype "passive"))
    )
    (net (code "49") (name "VDIO_LMS") (class "Default")
      (node (ref "C177") (pin "2") (pinfunction "2_2") (pintype "passive"))
      (node (ref "R92") (pin "1") (pinfunction "1_1") (pintype "passive"))
      (node (ref "R93") (pin "1") (pinfunction "1_1") (pintype "passive"))
      (node (ref "R94") (pin "1") (pinfunction "1_1") (pintype "passive"))
      (node (ref "R95") (pin "1") (pinfunction "1_1") (pintype "passive"))
      (node (ref "R96") (pin "1") (pinfunction "1_1") (pintype "passive"))
    )
  )
)
